# LED_strip.net
KiCad netlist of a schematic drawn in EAGLE
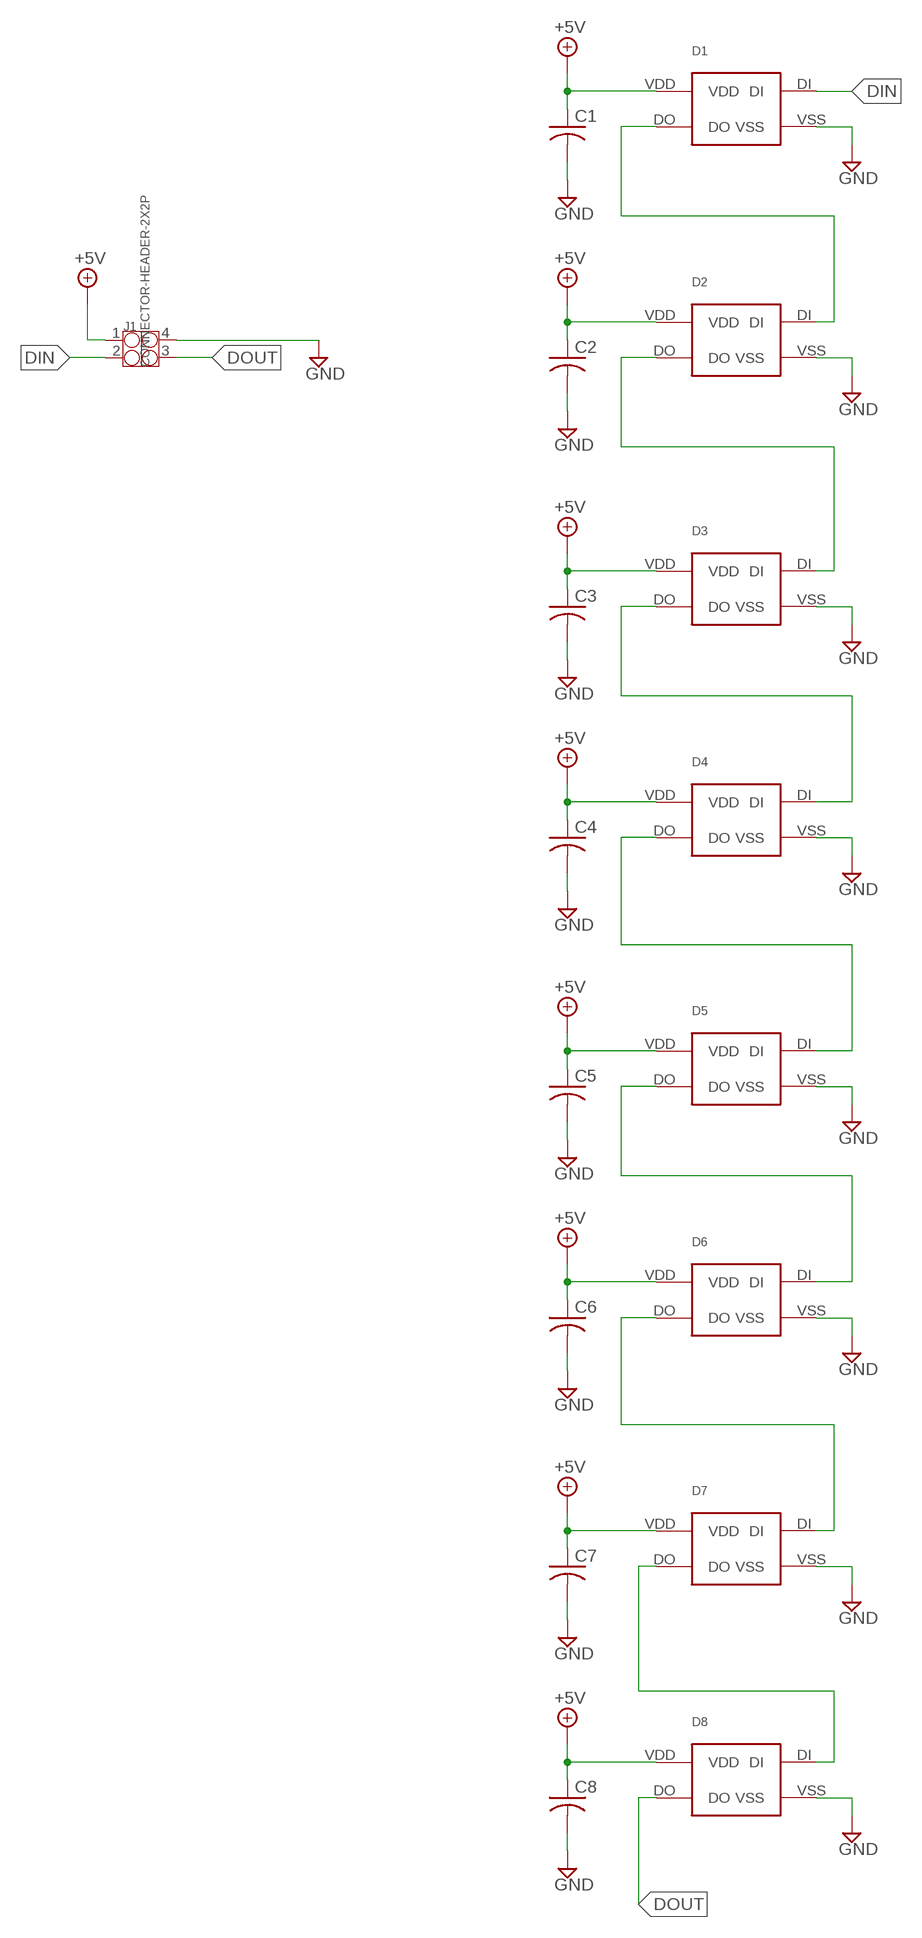
[diagram p0: schematic, sheet 1]

(export (version "E")
  (design (tool "Eeschema 10.0.6"))
  (components
    (comp (ref "C1")
      (value "C-USC0603K")
      (footprint "eagle-import:C0603K")
      (libsource (lib "eagle-import") (part "C-USC0603K"))
    )
    (comp (ref "C2")
      (value "C-USC0603K")
      (footprint "eagle-import:C0603K")
      (libsource (lib "eagle-import") (part "C-USC0603K"))
    )
    (comp (ref "C3")
      (value "C-USC0603K")
      (footprint "eagle-import:C0603K")
      (libsource (lib "eagle-import") (part "C-USC0603K"))
    )
    (comp (ref "C4")
      (value "C-USC0603K")
      (footprint "eagle-import:C0603K")
      (libsource (lib "eagle-import") (part "C-USC0603K"))
    )
    (comp (ref "C5")
      (value "C-USC0603K")
      (footprint "eagle-import:C0603K")
      (libsource (lib "eagle-import") (part "C-USC0603K"))
    )
    (comp (ref "C6")
      (value "C-USC0603K")
      (footprint "eagle-import:C0603K")
      (libsource (lib "eagle-import") (part "C-USC0603K"))
    )
    (comp (ref "C7")
      (value "C-USC0603K")
      (footprint "eagle-import:C0603K")
      (libsource (lib "eagle-import") (part "C-USC0603K"))
    )
    (comp (ref "C8")
      (value "C-USC0603K")
      (footprint "eagle-import:C0603K")
      (libsource (lib "eagle-import") (part "C-USC0603K"))
    )
    (comp (ref "D1")
      (value "WS2812B")
      (footprint "eagle-import:WS2812B")
      (libsource (lib "eagle-import") (part "WS2812B"))
    )
    (comp (ref "D2")
      (value "WS2812B")
      (footprint "eagle-import:WS2812B")
      (libsource (lib "eagle-import") (part "WS2812B"))
    )
    (comp (ref "D3")
      (value "WS2812B")
      (footprint "eagle-import:WS2812B")
      (libsource (lib "eagle-import") (part "WS2812B"))
    )
    (comp (ref "D4")
      (value "WS2812B")
      (footprint "eagle-import:WS2812B")
      (libsource (lib "eagle-import") (part "WS2812B"))
    )
    (comp (ref "D5")
      (value "WS2812B")
      (footprint "eagle-import:WS2812B")
      (libsource (lib "eagle-import") (part "WS2812B"))
    )
    (comp (ref "D6")
      (value "WS2812B")
      (footprint "eagle-import:WS2812B")
      (libsource (lib "eagle-import") (part "WS2812B"))
    )
    (comp (ref "D7")
      (value "WS2812B")
      (footprint "eagle-import:WS2812B")
      (libsource (lib "eagle-import") (part "WS2812B"))
    )
    (comp (ref "D8")
      (value "WS2812B")
      (footprint "eagle-import:WS2812B")
      (libsource (lib "eagle-import") (part "WS2812B"))
    )
    (comp (ref "J1")
      (value "CONNECTOR-HEADER-2X2P")
      (footprint "eagle-import:2X2P-2.54")
      (libsource (lib "eagle-import") (part "CONNECTOR-HEADER-2X2P"))
    )
  )
  (nets
    (net (code "1") (name "+5V") (class "Default")
      (node (ref "C1") (pin "1") (pinfunction "1_1") (pintype "passive"))
      (node (ref "C2") (pin "1") (pinfunction "1_1") (pintype "passive"))
      (node (ref "C3") (pin "1") (pinfunction "1_1") (pintype "passive"))
      (node (ref "C4") (pin "1") (pinfunction "1_1") (pintype "passive"))
      (node (ref "C5") (pin "1") (pinfunction "1_1") (pintype "passive"))
      (node (ref "C6") (pin "1") (pinfunction "1_1") (pintype "passive"))
      (node (ref "C7") (pin "1") (pinfunction "1_1") (pintype "passive"))
      (node (ref "C8") (pin "1") (pinfunction "1_1") (pintype "passive"))
      (node (ref "D1") (pin "VDD") (pinfunction "VDD_VDD") (pintype "bidirectional"))
      (node (ref "D2") (pin "VDD") (pinfunction "VDD_VDD") (pintype "bidirectional"))
      (node (ref "D3") (pin "VDD") (pinfunction "VDD_VDD") (pintype "bidirectional"))
      (node (ref "D4") (pin "VDD") (pinfunction "VDD_VDD") (pintype "bidirectional"))
      (node (ref "D5") (pin "VDD") (pinfunction "VDD_VDD") (pintype "bidirectional"))
      (node (ref "D6") (pin "VDD") (pinfunction "VDD_VDD") (pintype "bidirectional"))
      (node (ref "D7") (pin "VDD") (pinfunction "VDD_VDD") (pintype "bidirectional"))
      (node (ref "D8") (pin "VDD") (pinfunction "VDD_VDD") (pintype "bidirectional"))
      (node (ref "J1") (pin "1") (pinfunction "1_1") (pintype "bidirectional"))
    )
    (net (code "2") (name "DIN") (class "Default")
      (node (ref "D1") (pin "DI") (pinfunction "DI_DI") (pintype "bidirectional"))
      (node (ref "J1") (pin "2") (pinfunction "2_2") (pintype "bidirectional"))
    )
    (net (code "3") (name "DOUT") (class "Default")
      (node (ref "D8") (pin "DO") (pinfunction "DO_DO") (pintype "bidirectional"))
      (node (ref "J1") (pin "3") (pinfunction "3_3") (pintype "bidirectional"))
    )
    (net (code "4") (name "GND") (class "Default")
      (node (ref "C1") (pin "2") (pinfunction "2_2") (pintype "passive"))
      (node (ref "C2") (pin "2") (pinfunction "2_2") (pintype "passive"))
      (node (ref "C3") (pin "2") (pinfunction "2_2") (pintype "passive"))
      (node (ref "C4") (pin "2") (pinfunction "2_2") (pintype "passive"))
      (node (ref "C5") (pin "2") (pinfunction "2_2") (pintype "passive"))
      (node (ref "C6") (pin "2") (pinfunction "2_2") (pintype "passive"))
      (node (ref "C7") (pin "2") (pinfunction "2_2") (pintype "passive"))
      (node (ref "C8") (pin "2") (pinfunction "2_2") (pintype "passive"))
      (node (ref "D1") (pin "VSS") (pinfunction "VSS_VSS") (pintype "bidirectional"))
      (node (ref "D2") (pin "VSS") (pinfunction "VSS_VSS") (pintype "bidirectional"))
      (node (ref "D3") (pin "VSS") (pinfunction "VSS_VSS") (pintype "bidirectional"))
      (node (ref "D4") (pin "VSS") (pinfunction "VSS_VSS") (pintype "bidirectional"))
      (node (ref "D5") (pin "VSS") (pinfunction "VSS_VSS") (pintype "bidirectional"))
      (node (ref "D6") (pin "VSS") (pinfunction "VSS_VSS") (pintype "bidirectional"))
      (node (ref "D7") (pin "VSS") (pinfunction "VSS_VSS") (pintype "bidirectional"))
      (node (ref "D8") (pin "VSS") (pinfunction "VSS_VSS") (pintype "bidirectional"))
      (node (ref "J1") (pin "4") (pinfunction "4_4") (pintype "bidirectional"))
    )
    (net (code "5") (name "Net-(D1-PadDO)") (class "Default")
      (node (ref "D1") (pin "DO") (pinfunction "DO_DO") (pintype "bidirectional"))
      (node (ref "D2") (pin "DI") (pinfunction "DI_DI") (pintype "bidirectional"))
    )
    (net (code "6") (name "Net-(D2-PadDO)") (class "Default")
      (node (ref "D2") (pin "DO") (pinfunction "DO_DO") (pintype "bidirectional"))
      (node (ref "D3") (pin "DI") (pinfunction "DI_DI") (pintype "bidirectional"))
    )
    (net (code "7") (name "Net-(D3-PadDO)") (class "Default")
      (node (ref "D3") (pin "DO") (pinfunction "DO_DO") (pintype "bidirectional"))
      (node (ref "D4") (pin "DI") (pinfunction "DI_DI") (pintype "bidirectional"))
    )
    (net (code "8") (name "Net-(D4-PadDO)") (class "Default")
      (node (ref "D4") (pin "DO") (pinfunction "DO_DO") (pintype "bidirectional"))
      (node (ref "D5") (pin "DI") (pinfunction "DI_DI") (pintype "bidirectional"))
    )
    (net (code "9") (name "Net-(D5-PadDO)") (class "Default")
      (node (ref "D5") (pin "DO") (pinfunction "DO_DO") (pintype "bidirectional"))
      (node (ref "D6") (pin "DI") (pinfunction "DI_DI") (pintype "bidirectional"))
    )
    (net (code "10") (name "Net-(D6-PadDO)") (class "Default")
      (node (ref "D6") (pin "DO") (pinfunction "DO_DO") (pintype "bidirectional"))
      (node (ref "D7") (pin "DI") (pinfunction "DI_DI") (pintype "bidirectional"))
    )
    (net (code "11") (name "Net-(D7-PadDO)") (class "Default")
      (node (ref "D7") (pin "DO") (pinfunction "DO_DO") (pintype "bidirectional"))
      (node (ref "D8") (pin "DI") (pinfunction "DI_DI") (pintype "bidirectional"))
    )
  )
)
